# 3phaseBridgeRecitifed.net
KiCad netlist of a schematic drawn in Altium Designer
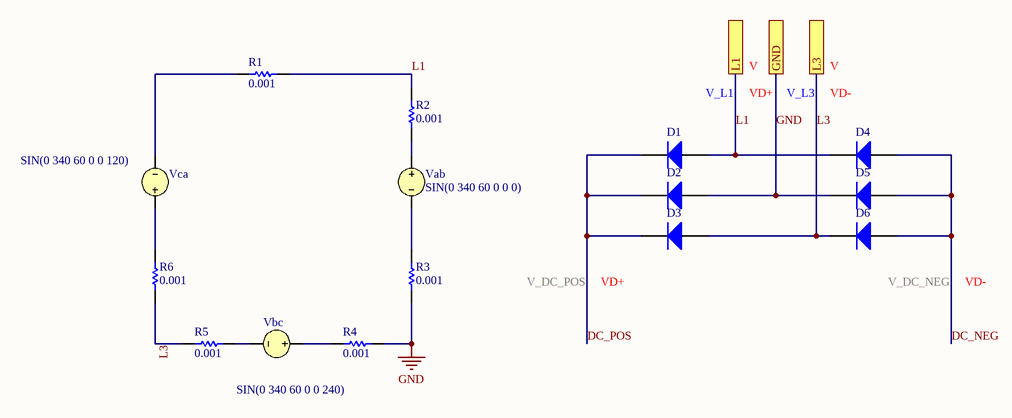
[diagram p0: 3phaseBridgeRecitifed.SchDoc]

(export (version "E")
  (design (tool "Eeschema 10.0.6"))
  (components
    (comp (ref "D1") (value "Diode") (libsource (lib "Simulation Generic Components") (part "Diode")))
    (comp (ref "D2") (value "Diode") (libsource (lib "Simulation Generic Components") (part "Diode")))
    (comp (ref "D3") (value "Diode") (libsource (lib "Simulation Generic Components") (part "Diode")))
    (comp (ref "D4") (value "Diode") (libsource (lib "Simulation Generic Components") (part "Diode")))
    (comp (ref "D5") (value "Diode") (libsource (lib "Simulation Generic Components") (part "Diode")))
    (comp (ref "D6") (value "Diode") (libsource (lib "Simulation Generic Components") (part "Diode")))
    (comp (ref "R1")
      (value "0.001")
      (description "Resistor")
      (libsource (lib "Simulation Generic Components") (part "Resistor"))
    )
    (comp (ref "R2")
      (value "0.001")
      (description "Resistor")
      (libsource (lib "Simulation Generic Components") (part "Resistor"))
    )
    (comp (ref "R3")
      (value "0.001")
      (description "Resistor")
      (libsource (lib "Simulation Generic Components") (part "Resistor"))
    )
    (comp (ref "R4")
      (value "0.001")
      (description "Resistor")
      (libsource (lib "Simulation Generic Components") (part "Resistor"))
    )
    (comp (ref "R5")
      (value "0.001")
      (description "Resistor")
      (libsource (lib "Simulation Generic Components") (part "Resistor"))
    )
    (comp (ref "R6")
      (value "0.001")
      (description "Resistor")
      (libsource (lib "Simulation Generic Components") (part "Resistor"))
    )
    (comp (ref "Vab")
      (value "SIN(0 340 60 0 0 0)")
      (description "Voltage Source")
      (fields (field (name "PUBLISHER") "Altium Limited"))
      (libsource (lib "Simulation Generic Components") (part "VSRC"))
    )
    (comp (ref "Vbc")
      (value "SIN(0 340 60 0 0 240)")
      (description "Voltage Source")
      (fields (field (name "PUBLISHER") "Altium Limited"))
      (libsource (lib "Simulation Generic Components") (part "VSRC"))
    )
    (comp (ref "Vca")
      (value "SIN(0 340 60 0 0 120)")
      (description "Voltage Source")
      (fields (field (name "PUBLISHER") "Altium Limited"))
      (libsource (lib "Simulation Generic Components") (part "VSRC"))
    )
  )
  (nets
    (net (code "1") (name "/DC_NEG") (class "Default")
      (node (ref "D4") (pin "1") (pinfunction "A_1") (pintype "passive"))
      (node (ref "D5") (pin "1") (pinfunction "A_1") (pintype "passive"))
      (node (ref "D6") (pin "1") (pinfunction "A_1") (pintype "passive"))
    )
    (net (code "2") (name "/DC_POS") (class "Default")
      (node (ref "D1") (pin "2") (pinfunction "K_2") (pintype "passive"))
      (node (ref "D2") (pin "2") (pinfunction "K_2") (pintype "passive"))
      (node (ref "D3") (pin "2") (pinfunction "K_2") (pintype "passive"))
    )
    (net (code "3") (name "/L1") (class "Default")
      (node (ref "D1") (pin "1") (pinfunction "A_1") (pintype "passive"))
      (node (ref "D4") (pin "2") (pinfunction "K_2") (pintype "passive"))
      (node (ref "R1") (pin "2") (pinfunction "2_2") (pintype "passive"))
      (node (ref "R2") (pin "1") (pinfunction "1_1") (pintype "passive"))
    )
    (net (code "4") (name "/L3") (class "Default")
      (node (ref "D3") (pin "1") (pinfunction "A_1") (pintype "passive"))
      (node (ref "D6") (pin "2") (pinfunction "K_2") (pintype "passive"))
      (node (ref "R5") (pin "1") (pinfunction "1_1") (pintype "passive"))
      (node (ref "R6") (pin "1") (pinfunction "1_1") (pintype "passive"))
    )
    (net (code "5") (name "GND") (class "Default")
      (node (ref "D2") (pin "1") (pinfunction "A_1") (pintype "passive"))
      (node (ref "D5") (pin "2") (pinfunction "K_2") (pintype "passive"))
      (node (ref "R3") (pin "1") (pinfunction "1_1") (pintype "passive"))
      (node (ref "R4") (pin "2") (pinfunction "2_2") (pintype "passive"))
    )
    (net (code "6") (name "Net-(R1-Pad1)") (class "Default")
      (node (ref "R1") (pin "1") (pinfunction "1_1") (pintype "passive"))
      (node (ref "Vca") (pin "2") (pinfunction "2_2") (pintype "passive"))
    )
    (net (code "7") (name "Net-(R2-Pad2)") (class "Default")
      (node (ref "R2") (pin "2") (pinfunction "2_2") (pintype "passive"))
      (node (ref "Vab") (pin "1") (pinfunction "1_1") (pintype "passive"))
    )
    (net (code "8") (name "Net-(R3-Pad2)") (class "Default")
      (node (ref "R3") (pin "2") (pinfunction "2_2") (pintype "passive"))
      (node (ref "Vab") (pin "2") (pinfunction "2_2") (pintype "passive"))
    )
    (net (code "9") (name "Net-(R4-Pad1)") (class "Default")
      (node (ref "R4") (pin "1") (pinfunction "1_1") (pintype "passive"))
      (node (ref "Vbc") (pin "1") (pinfunction "1_1") (pintype "passive"))
    )
    (net (code "10") (name "Net-(R5-Pad2)") (class "Default")
      (node (ref "R5") (pin "2") (pinfunction "2_2") (pintype "passive"))
      (node (ref "Vbc") (pin "2") (pinfunction "2_2") (pintype "passive"))
    )
    (net (code "11") (name "Net-(R6-Pad2)") (class "Default")
      (node (ref "R6") (pin "2") (pinfunction "2_2") (pintype "passive"))
      (node (ref "Vca") (pin "1") (pinfunction "1_1") (pintype "passive"))
    )
  )
)
